# dueSkel.net
KiCad netlist of a schematic drawn in EAGLE
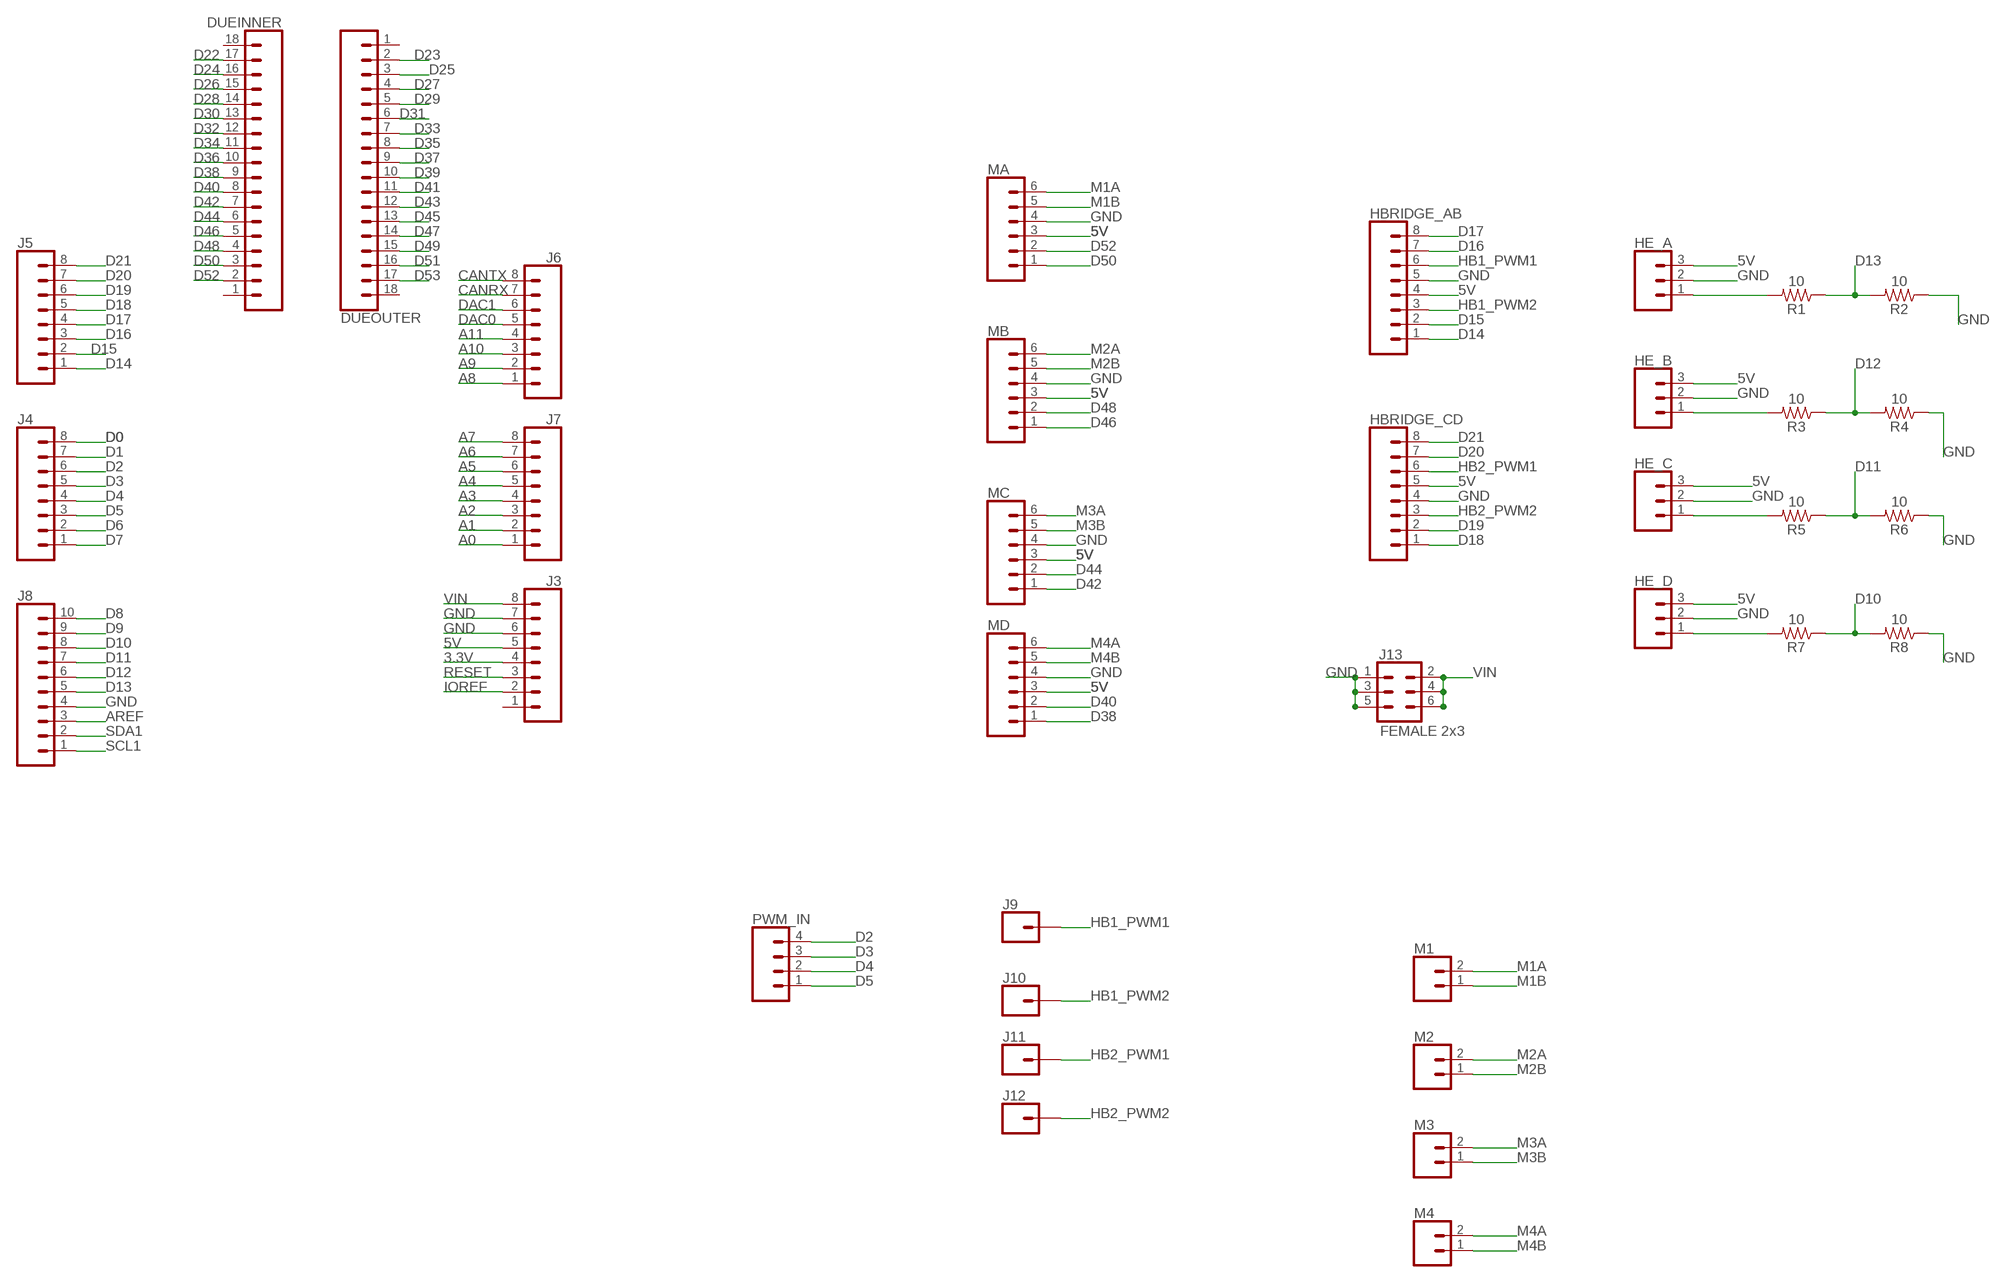
[diagram p0: schematic, sheet 1]

(export (version "E")
  (design (tool "Eeschema 10.0.6"))
  (components
    (comp (ref "DUEINNER")
      (value "CONN_18")
      (footprint "eagle-import:1X18")
      (libsource (lib "eagle-import") (part "CONN_18"))
    )
    (comp (ref "DUEOUTER")
      (value "CONN_18")
      (footprint "eagle-import:1X18")
      (libsource (lib "eagle-import") (part "CONN_18"))
    )
    (comp (ref "HBRIDGE_AB")
      (value "CONN_08\"")
      (footprint "eagle-import:1X08")
      (libsource (lib "eagle-import") (part "CONN_08{dblquote}"))
    )
    (comp (ref "HBRIDGE_CD")
      (value "CONN_08\"")
      (footprint "eagle-import:1X08")
      (libsource (lib "eagle-import") (part "CONN_08{dblquote}"))
    )
    (comp (ref "HE_A")
      (value "CONN_03")
      (footprint "eagle-import:1X03")
      (libsource (lib "eagle-import") (part "CONN_03"))
    )
    (comp (ref "HE_B")
      (value "CONN_03")
      (footprint "eagle-import:1X03")
      (libsource (lib "eagle-import") (part "CONN_03"))
    )
    (comp (ref "HE_C")
      (value "CONN_03")
      (footprint "eagle-import:1X03")
      (libsource (lib "eagle-import") (part "CONN_03"))
    )
    (comp (ref "HE_D")
      (value "CONN_03")
      (footprint "eagle-import:1X03")
      (libsource (lib "eagle-import") (part "CONN_03"))
    )
    (comp (ref "J3")
      (value "CONN_08\"")
      (footprint "eagle-import:1X08")
      (libsource (lib "eagle-import") (part "CONN_08{dblquote}"))
    )
    (comp (ref "J4")
      (value "CONN_08\"")
      (footprint "eagle-import:1X08")
      (libsource (lib "eagle-import") (part "CONN_08{dblquote}"))
    )
    (comp (ref "J5")
      (value "CONN_08\"")
      (footprint "eagle-import:1X08")
      (libsource (lib "eagle-import") (part "CONN_08{dblquote}"))
    )
    (comp (ref "J6")
      (value "CONN_08\"")
      (footprint "eagle-import:1X08")
      (libsource (lib "eagle-import") (part "CONN_08{dblquote}"))
    )
    (comp (ref "J7")
      (value "CONN_08\"")
      (footprint "eagle-import:1X08")
      (libsource (lib "eagle-import") (part "CONN_08{dblquote}"))
    )
    (comp (ref "J8")
      (value "CONN_10\"")
      (footprint "eagle-import:1X10")
      (libsource (lib "eagle-import") (part "CONN_10{dblquote}"))
    )
    (comp (ref "J9")
      (value "CONN_01")
      (footprint "eagle-import:1X01")
      (libsource (lib "eagle-import") (part "CONN_01"))
    )
    (comp (ref "J10")
      (value "CONN_01")
      (footprint "eagle-import:1X01")
      (libsource (lib "eagle-import") (part "CONN_01"))
    )
    (comp (ref "J11")
      (value "CONN_01")
      (footprint "eagle-import:1X01")
      (libsource (lib "eagle-import") (part "CONN_01"))
    )
    (comp (ref "J12")
      (value "CONN_01")
      (footprint "eagle-import:1X01")
      (libsource (lib "eagle-import") (part "CONN_01"))
    )
    (comp (ref "J13")
      (value "FEMALE 2x3")
      (footprint "eagle-import:2X3")
      (libsource (lib "eagle-import") (part "CONN_03X2FEMALE"))
    )
    (comp (ref "M1")
      (value "CONN_02")
      (footprint "eagle-import:1X02")
      (libsource (lib "eagle-import") (part "CONN_02"))
    )
    (comp (ref "M2")
      (value "CONN_02")
      (footprint "eagle-import:1X02")
      (libsource (lib "eagle-import") (part "CONN_02"))
    )
    (comp (ref "M3")
      (value "CONN_02")
      (footprint "eagle-import:1X02")
      (libsource (lib "eagle-import") (part "CONN_02"))
    )
    (comp (ref "M4")
      (value "CONN_02")
      (footprint "eagle-import:1X02")
      (libsource (lib "eagle-import") (part "CONN_02"))
    )
    (comp (ref "MA")
      (value "CONN_06SILK_FEMALE_PTH")
      (footprint "eagle-import:1X06")
      (libsource (lib "eagle-import") (part "CONN_06SILK_FEMALE_PTH"))
    )
    (comp (ref "MB")
      (value "CONN_06SILK_FEMALE_PTH")
      (footprint "eagle-import:1X06")
      (libsource (lib "eagle-import") (part "CONN_06SILK_FEMALE_PTH"))
    )
    (comp (ref "MC")
      (value "CONN_06SILK_FEMALE_PTH")
      (footprint "eagle-import:1X06")
      (libsource (lib "eagle-import") (part "CONN_06SILK_FEMALE_PTH"))
    )
    (comp (ref "MD")
      (value "CONN_06SILK_FEMALE_PTH")
      (footprint "eagle-import:1X06")
      (libsource (lib "eagle-import") (part "CONN_06SILK_FEMALE_PTH"))
    )
    (comp (ref "PWM_IN")
      (value "CONN_04")
      (footprint "eagle-import:1X04")
      (libsource (lib "eagle-import") (part "CONN_04"))
    )
    (comp (ref "R1")
      (value "10")
      (footprint "eagle-import:AXIAL-0.3")
      (libsource (lib "eagle-import") (part "10OHM-HORIZ-1/4W-1%"))
    )
    (comp (ref "R2")
      (value "10")
      (footprint "eagle-import:AXIAL-0.3")
      (libsource (lib "eagle-import") (part "10OHM-HORIZ-1/4W-1%"))
    )
    (comp (ref "R3")
      (value "10")
      (footprint "eagle-import:AXIAL-0.3")
      (libsource (lib "eagle-import") (part "10OHM-HORIZ-1/4W-1%"))
    )
    (comp (ref "R4")
      (value "10")
      (footprint "eagle-import:AXIAL-0.3")
      (libsource (lib "eagle-import") (part "10OHM-HORIZ-1/4W-1%"))
    )
    (comp (ref "R5")
      (value "10")
      (footprint "eagle-import:AXIAL-0.3")
      (libsource (lib "eagle-import") (part "10OHM-HORIZ-1/4W-1%"))
    )
    (comp (ref "R6")
      (value "10")
      (footprint "eagle-import:AXIAL-0.3")
      (libsource (lib "eagle-import") (part "10OHM-HORIZ-1/4W-1%"))
    )
    (comp (ref "R7")
      (value "10")
      (footprint "eagle-import:AXIAL-0.3")
      (libsource (lib "eagle-import") (part "10OHM-HORIZ-1/4W-1%"))
    )
    (comp (ref "R8")
      (value "10")
      (footprint "eagle-import:AXIAL-0.3")
      (libsource (lib "eagle-import") (part "10OHM-HORIZ-1/4W-1%"))
    )
  )
  (nets
    (net (code "1") (name "/3.3V") (class "Default")
      (node (ref "J3") (pin "4") (pinfunction "4_4") (pintype "passive"))
    )
    (net (code "2") (name "/5V") (class "Default")
      (node (ref "HBRIDGE_AB") (pin "4") (pinfunction "4_4") (pintype "passive"))
      (node (ref "HBRIDGE_CD") (pin "5") (pinfunction "5_5") (pintype "passive"))
      (node (ref "HE_A") (pin "3") (pinfunction "3_3") (pintype "passive"))
      (node (ref "HE_B") (pin "3") (pinfunction "3_3") (pintype "passive"))
      (node (ref "HE_C") (pin "3") (pinfunction "3_3") (pintype "passive"))
      (node (ref "HE_D") (pin "3") (pinfunction "3_3") (pintype "passive"))
      (node (ref "J3") (pin "5") (pinfunction "5_5") (pintype "passive"))
      (node (ref "MA") (pin "3") (pinfunction "3_3") (pintype "passive"))
      (node (ref "MB") (pin "3") (pinfunction "3_3") (pintype "passive"))
      (node (ref "MC") (pin "3") (pinfunction "3_3") (pintype "passive"))
      (node (ref "MD") (pin "3") (pinfunction "3_3") (pintype "passive"))
    )
    (net (code "3") (name "/A0") (class "Default")
      (node (ref "J7") (pin "1") (pinfunction "1_1") (pintype "passive"))
    )
    (net (code "4") (name "/A1") (class "Default")
      (node (ref "J7") (pin "2") (pinfunction "2_2") (pintype "passive"))
    )
    (net (code "5") (name "/A2") (class "Default")
      (node (ref "J7") (pin "3") (pinfunction "3_3") (pintype "passive"))
    )
    (net (code "6") (name "/A3") (class "Default")
      (node (ref "J7") (pin "4") (pinfunction "4_4") (pintype "passive"))
    )
    (net (code "7") (name "/A4") (class "Default")
      (node (ref "J7") (pin "5") (pinfunction "5_5") (pintype "passive"))
    )
    (net (code "8") (name "/A5") (class "Default")
      (node (ref "J7") (pin "6") (pinfunction "6_6") (pintype "passive"))
    )
    (net (code "9") (name "/A6") (class "Default")
      (node (ref "J7") (pin "7") (pinfunction "7_7") (pintype "passive"))
    )
    (net (code "10") (name "/A7") (class "Default")
      (node (ref "J7") (pin "8") (pinfunction "8_8") (pintype "passive"))
    )
    (net (code "11") (name "/A8") (class "Default")
      (node (ref "J6") (pin "1") (pinfunction "1_1") (pintype "passive"))
    )
    (net (code "12") (name "/A9") (class "Default")
      (node (ref "J6") (pin "2") (pinfunction "2_2") (pintype "passive"))
    )
    (net (code "13") (name "/A10") (class "Default")
      (node (ref "J6") (pin "3") (pinfunction "3_3") (pintype "passive"))
    )
    (net (code "14") (name "/A11") (class "Default")
      (node (ref "J6") (pin "4") (pinfunction "4_4") (pintype "passive"))
    )
    (net (code "15") (name "/AREF") (class "Default")
      (node (ref "J8") (pin "3") (pinfunction "3_3") (pintype "passive"))
    )
    (net (code "16") (name "/CANRX") (class "Default")
      (node (ref "J6") (pin "7") (pinfunction "7_7") (pintype "passive"))
    )
    (net (code "17") (name "/CANTX") (class "Default")
      (node (ref "J6") (pin "8") (pinfunction "8_8") (pintype "passive"))
    )
    (net (code "18") (name "/D0") (class "Default")
      (node (ref "J4") (pin "8") (pinfunction "8_8") (pintype "passive"))
    )
    (net (code "19") (name "/D1") (class "Default")
      (node (ref "J4") (pin "7") (pinfunction "7_7") (pintype "passive"))
    )
    (net (code "20") (name "/D2") (class "Default")
      (node (ref "J4") (pin "6") (pinfunction "6_6") (pintype "passive"))
      (node (ref "PWM_IN") (pin "4") (pinfunction "4_4") (pintype "passive"))
    )
    (net (code "21") (name "/D3") (class "Default")
      (node (ref "J4") (pin "5") (pinfunction "5_5") (pintype "passive"))
      (node (ref "PWM_IN") (pin "3") (pinfunction "3_3") (pintype "passive"))
    )
    (net (code "22") (name "/D4") (class "Default")
      (node (ref "J4") (pin "4") (pinfunction "4_4") (pintype "passive"))
      (node (ref "PWM_IN") (pin "2") (pinfunction "2_2") (pintype "passive"))
    )
    (net (code "23") (name "/D5") (class "Default")
      (node (ref "J4") (pin "3") (pinfunction "3_3") (pintype "passive"))
      (node (ref "PWM_IN") (pin "1") (pinfunction "1_1") (pintype "passive"))
    )
    (net (code "24") (name "/D6") (class "Default")
      (node (ref "J4") (pin "2") (pinfunction "2_2") (pintype "passive"))
    )
    (net (code "25") (name "/D7") (class "Default")
      (node (ref "J4") (pin "1") (pinfunction "1_1") (pintype "passive"))
    )
    (net (code "26") (name "/D8") (class "Default")
      (node (ref "J8") (pin "10") (pinfunction "10_10") (pintype "passive"))
    )
    (net (code "27") (name "/D9") (class "Default")
      (node (ref "J8") (pin "9") (pinfunction "9_9") (pintype "passive"))
    )
    (net (code "28") (name "/D10") (class "Default")
      (node (ref "J8") (pin "8") (pinfunction "8_8") (pintype "passive"))
      (node (ref "R7") (pin "P$1") (pinfunction "1_P$1") (pintype "passive"))
      (node (ref "R8") (pin "P$2") (pinfunction "2_P$2") (pintype "passive"))
    )
    (net (code "29") (name "/D11") (class "Default")
      (node (ref "J8") (pin "7") (pinfunction "7_7") (pintype "passive"))
      (node (ref "R5") (pin "P$1") (pinfunction "1_P$1") (pintype "passive"))
      (node (ref "R6") (pin "P$2") (pinfunction "2_P$2") (pintype "passive"))
    )
    (net (code "30") (name "/D12") (class "Default")
      (node (ref "J8") (pin "6") (pinfunction "6_6") (pintype "passive"))
      (node (ref "R3") (pin "P$1") (pinfunction "1_P$1") (pintype "passive"))
      (node (ref "R4") (pin "P$2") (pinfunction "2_P$2") (pintype "passive"))
    )
    (net (code "31") (name "/D13") (class "Default")
      (node (ref "J8") (pin "5") (pinfunction "5_5") (pintype "passive"))
      (node (ref "R1") (pin "P$1") (pinfunction "1_P$1") (pintype "passive"))
      (node (ref "R2") (pin "P$2") (pinfunction "2_P$2") (pintype "passive"))
    )
    (net (code "32") (name "/D14") (class "Default")
      (node (ref "HBRIDGE_AB") (pin "1") (pinfunction "1_1") (pintype "passive"))
      (node (ref "J5") (pin "1") (pinfunction "1_1") (pintype "passive"))
    )
    (net (code "33") (name "/D15") (class "Default")
      (node (ref "HBRIDGE_AB") (pin "2") (pinfunction "2_2") (pintype "passive"))
      (node (ref "J5") (pin "2") (pinfunction "2_2") (pintype "passive"))
    )
    (net (code "34") (name "/D16") (class "Default")
      (node (ref "HBRIDGE_AB") (pin "7") (pinfunction "7_7") (pintype "passive"))
      (node (ref "J5") (pin "3") (pinfunction "3_3") (pintype "passive"))
    )
    (net (code "35") (name "/D17") (class "Default")
      (node (ref "HBRIDGE_AB") (pin "8") (pinfunction "8_8") (pintype "passive"))
      (node (ref "J5") (pin "4") (pinfunction "4_4") (pintype "passive"))
    )
    (net (code "36") (name "/D18") (class "Default")
      (node (ref "HBRIDGE_CD") (pin "1") (pinfunction "1_1") (pintype "passive"))
      (node (ref "J5") (pin "5") (pinfunction "5_5") (pintype "passive"))
    )
    (net (code "37") (name "/D19") (class "Default")
      (node (ref "HBRIDGE_CD") (pin "2") (pinfunction "2_2") (pintype "passive"))
      (node (ref "J5") (pin "6") (pinfunction "6_6") (pintype "passive"))
    )
    (net (code "38") (name "/D20") (class "Default")
      (node (ref "HBRIDGE_CD") (pin "7") (pinfunction "7_7") (pintype "passive"))
      (node (ref "J5") (pin "7") (pinfunction "7_7") (pintype "passive"))
    )
    (net (code "39") (name "/D21") (class "Default")
      (node (ref "HBRIDGE_CD") (pin "8") (pinfunction "8_8") (pintype "passive"))
      (node (ref "J5") (pin "8") (pinfunction "8_8") (pintype "passive"))
    )
    (net (code "40") (name "/D22") (class "Default")
      (node (ref "DUEINNER") (pin "17") (pinfunction "17_17") (pintype "passive"))
    )
    (net (code "41") (name "/D23") (class "Default")
      (node (ref "DUEOUTER") (pin "2") (pinfunction "2_2") (pintype "passive"))
    )
    (net (code "42") (name "/D24") (class "Default")
      (node (ref "DUEINNER") (pin "16") (pinfunction "16_16") (pintype "passive"))
    )
    (net (code "43") (name "/D25") (class "Default")
      (node (ref "DUEOUTER") (pin "3") (pinfunction "3_3") (pintype "passive"))
    )
    (net (code "44") (name "/D26") (class "Default")
      (node (ref "DUEINNER") (pin "15") (pinfunction "15_15") (pintype "passive"))
    )
    (net (code "45") (name "/D27") (class "Default")
      (node (ref "DUEOUTER") (pin "4") (pinfunction "4_4") (pintype "passive"))
    )
    (net (code "46") (name "/D28") (class "Default")
      (node (ref "DUEINNER") (pin "14") (pinfunction "14_14") (pintype "passive"))
    )
    (net (code "47") (name "/D29") (class "Default")
      (node (ref "DUEOUTER") (pin "5") (pinfunction "5_5") (pintype "passive"))
    )
    (net (code "48") (name "/D30") (class "Default")
      (node (ref "DUEINNER") (pin "13") (pinfunction "13_13") (pintype "passive"))
    )
    (net (code "49") (name "/D31") (class "Default")
      (node (ref "DUEOUTER") (pin "6") (pinfunction "6_6") (pintype "passive"))
    )
    (net (code "50") (name "/D32") (class "Default")
      (node (ref "DUEINNER") (pin "12") (pinfunction "12_12") (pintype "passive"))
    )
    (net (code "51") (name "/D33") (class "Default")
      (node (ref "DUEOUTER") (pin "7") (pinfunction "7_7") (pintype "passive"))
    )
    (net (code "52") (name "/D34") (class "Default")
      (node (ref "DUEINNER") (pin "11") (pinfunction "11_11") (pintype "passive"))
    )
    (net (code "53") (name "/D35") (class "Default")
      (node (ref "DUEOUTER") (pin "8") (pinfunction "8_8") (pintype "passive"))
    )
    (net (code "54") (name "/D36") (class "Default")
      (node (ref "DUEINNER") (pin "10") (pinfunction "10_10") (pintype "passive"))
    )
    (net (code "55") (name "/D37") (class "Default")
      (node (ref "DUEOUTER") (pin "9") (pinfunction "9_9") (pintype "passive"))
    )
    (net (code "56") (name "/D38") (class "Default")
      (node (ref "DUEINNER") (pin "9") (pinfunction "9_9") (pintype "passive"))
      (node (ref "MD") (pin "1") (pinfunction "1_1") (pintype "passive"))
    )
    (net (code "57") (name "/D39") (class "Default")
      (node (ref "DUEOUTER") (pin "10") (pinfunction "10_10") (pintype "passive"))
    )
    (net (code "58") (name "/D40") (class "Default")
      (node (ref "DUEINNER") (pin "8") (pinfunction "8_8") (pintype "passive"))
      (node (ref "MD") (pin "2") (pinfunction "2_2") (pintype "passive"))
    )
    (net (code "59") (name "/D41") (class "Default")
      (node (ref "DUEOUTER") (pin "11") (pinfunction "11_11") (pintype "passive"))
    )
    (net (code "60") (name "/D42") (class "Default")
      (node (ref "DUEINNER") (pin "7") (pinfunction "7_7") (pintype "passive"))
      (node (ref "MC") (pin "1") (pinfunction "1_1") (pintype "passive"))
    )
    (net (code "61") (name "/D43") (class "Default")
      (node (ref "DUEOUTER") (pin "12") (pinfunction "12_12") (pintype "passive"))
    )
    (net (code "62") (name "/D44") (class "Default")
      (node (ref "DUEINNER") (pin "6") (pinfunction "6_6") (pintype "passive"))
      (node (ref "MC") (pin "2") (pinfunction "2_2") (pintype "passive"))
    )
    (net (code "63") (name "/D45") (class "Default")
      (node (ref "DUEOUTER") (pin "13") (pinfunction "13_13") (pintype "passive"))
    )
    (net (code "64") (name "/D46") (class "Default")
      (node (ref "DUEINNER") (pin "5") (pinfunction "5_5") (pintype "passive"))
      (node (ref "MB") (pin "1") (pinfunction "1_1") (pintype "passive"))
    )
    (net (code "65") (name "/D47") (class "Default")
      (node (ref "DUEOUTER") (pin "14") (pinfunction "14_14") (pintype "passive"))
    )
    (net (code "66") (name "/D48") (class "Default")
      (node (ref "DUEINNER") (pin "4") (pinfunction "4_4") (pintype "passive"))
      (node (ref "MB") (pin "2") (pinfunction "2_2") (pintype "passive"))
    )
    (net (code "67") (name "/D49") (class "Default")
      (node (ref "DUEOUTER") (pin "15") (pinfunction "15_15") (pintype "passive"))
    )
    (net (code "68") (name "/D50") (class "Default")
      (node (ref "DUEINNER") (pin "3") (pinfunction "3_3") (pintype "passive"))
      (node (ref "MA") (pin "1") (pinfunction "1_1") (pintype "passive"))
    )
    (net (code "69") (name "/D51") (class "Default")
      (node (ref "DUEOUTER") (pin "16") (pinfunction "16_16") (pintype "passive"))
    )
    (net (code "70") (name "/D52") (class "Default")
      (node (ref "DUEINNER") (pin "2") (pinfunction "2_2") (pintype "passive"))
      (node (ref "MA") (pin "2") (pinfunction "2_2") (pintype "passive"))
    )
    (net (code "71") (name "/D53") (class "Default")
      (node (ref "DUEOUTER") (pin "17") (pinfunction "17_17") (pintype "passive"))
    )
    (net (code "72") (name "/DAC0") (class "Default")
      (node (ref "J6") (pin "5") (pinfunction "5_5") (pintype "passive"))
    )
    (net (code "73") (name "/DAC1") (class "Default")
      (node (ref "J6") (pin "6") (pinfunction "6_6") (pintype "passive"))
    )
    (net (code "74") (name "/GND") (class "Default")
      (node (ref "HBRIDGE_AB") (pin "5") (pinfunction "5_5") (pintype "passive"))
      (node (ref "HBRIDGE_CD") (pin "4") (pinfunction "4_4") (pintype "passive"))
      (node (ref "HE_A") (pin "2") (pinfunction "2_2") (pintype "passive"))
      (node (ref "HE_B") (pin "2") (pinfunction "2_2") (pintype "passive"))
      (node (ref "HE_C") (pin "2") (pinfunction "2_2") (pintype "passive"))
      (node (ref "HE_D") (pin "2") (pinfunction "2_2") (pintype "passive"))
      (node (ref "J13") (pin "1") (pinfunction "1_1") (pintype "bidirectional"))
      (node (ref "J13") (pin "3") (pinfunction "3_3") (pintype "bidirectional"))
      (node (ref "J13") (pin "5") (pinfunction "5_5") (pintype "bidirectional"))
      (node (ref "J3") (pin "6") (pinfunction "6_6") (pintype "passive"))
      (node (ref "J3") (pin "7") (pinfunction "7_7") (pintype "passive"))
      (node (ref "J8") (pin "4") (pinfunction "4_4") (pintype "passive"))
      (node (ref "MA") (pin "4") (pinfunction "4_4") (pintype "passive"))
      (node (ref "MB") (pin "4") (pinfunction "4_4") (pintype "passive"))
      (node (ref "MC") (pin "4") (pinfunction "4_4") (pintype "passive"))
      (node (ref "MD") (pin "4") (pinfunction "4_4") (pintype "passive"))
      (node (ref "R2") (pin "P$1") (pinfunction "1_P$1") (pintype "passive"))
      (node (ref "R4") (pin "P$1") (pinfunction "1_P$1") (pintype "passive"))
      (node (ref "R6") (pin "P$1") (pinfunction "1_P$1") (pintype "passive"))
      (node (ref "R8") (pin "P$1") (pinfunction "1_P$1") (pintype "passive"))
    )
    (net (code "75") (name "/HB1_PWM1") (class "Default")
      (node (ref "HBRIDGE_AB") (pin "6") (pinfunction "6_6") (pintype "passive"))
      (node (ref "J9") (pin "1") (pinfunction "1_1") (pintype "passive"))
    )
    (net (code "76") (name "/HB1_PWM2") (class "Default")
      (node (ref "HBRIDGE_AB") (pin "3") (pinfunction "3_3") (pintype "passive"))
      (node (ref "J10") (pin "1") (pinfunction "1_1") (pintype "passive"))
    )
    (net (code "77") (name "/HB2_PWM1") (class "Default")
      (node (ref "HBRIDGE_CD") (pin "6") (pinfunction "6_6") (pintype "passive"))
      (node (ref "J11") (pin "1") (pinfunction "1_1") (pintype "passive"))
    )
    (net (code "78") (name "/HB2_PWM2") (class "Default")
      (node (ref "HBRIDGE_CD") (pin "3") (pinfunction "3_3") (pintype "passive"))
      (node (ref "J12") (pin "1") (pinfunction "1_1") (pintype "passive"))
    )
    (net (code "79") (name "/IOREF") (class "Default")
      (node (ref "J3") (pin "2") (pinfunction "2_2") (pintype "passive"))
    )
    (net (code "80") (name "/M1A") (class "Default")
      (node (ref "M1") (pin "2") (pinfunction "2_2") (pintype "passive"))
      (node (ref "MA") (pin "6") (pinfunction "6_6") (pintype "passive"))
    )
    (net (code "81") (name "/M1B") (class "Default")
      (node (ref "M1") (pin "1") (pinfunction "1_1") (pintype "passive"))
      (node (ref "MA") (pin "5") (pinfunction "5_5") (pintype "passive"))
    )
    (net (code "82") (name "/M2A") (class "Default")
      (node (ref "M2") (pin "2") (pinfunction "2_2") (pintype "passive"))
      (node (ref "MB") (pin "6") (pinfunction "6_6") (pintype "passive"))
    )
    (net (code "83") (name "/M2B") (class "Default")
      (node (ref "M2") (pin "1") (pinfunction "1_1") (pintype "passive"))
      (node (ref "MB") (pin "5") (pinfunction "5_5") (pintype "passive"))
    )
    (net (code "84") (name "/M3A") (class "Default")
      (node (ref "M3") (pin "2") (pinfunction "2_2") (pintype "passive"))
      (node (ref "MC") (pin "6") (pinfunction "6_6") (pintype "passive"))
    )
    (net (code "85") (name "/M3B") (class "Default")
      (node (ref "M3") (pin "1") (pinfunction "1_1") (pintype "passive"))
      (node (ref "MC") (pin "5") (pinfunction "5_5") (pintype "passive"))
    )
    (net (code "86") (name "/M4A") (class "Default")
      (node (ref "M4") (pin "2") (pinfunction "2_2") (pintype "passive"))
      (node (ref "MD") (pin "6") (pinfunction "6_6") (pintype "passive"))
    )
    (net (code "87") (name "/M4B") (class "Default")
      (node (ref "M4") (pin "1") (pinfunction "1_1") (pintype "passive"))
      (node (ref "MD") (pin "5") (pinfunction "5_5") (pintype "passive"))
    )
    (net (code "88") (name "/RESET") (class "Default")
      (node (ref "J3") (pin "3") (pinfunction "3_3") (pintype "passive"))
    )
    (net (code "89") (name "/SCL1") (class "Default")
      (node (ref "J8") (pin "1") (pinfunction "1_1") (pintype "passive"))
    )
    (net (code "90") (name "/SDA1") (class "Default")
      (node (ref "J8") (pin "2") (pinfunction "2_2") (pintype "passive"))
    )
    (net (code "91") (name "/VIN") (class "Default")
      (node (ref "J13") (pin "2") (pinfunction "2_2") (pintype "bidirectional"))
      (node (ref "J13") (pin "4") (pinfunction "4_4") (pintype "bidirectional"))
      (node (ref "J13") (pin "6") (pinfunction "6_6") (pintype "bidirectional"))
      (node (ref "J3") (pin "8") (pinfunction "8_8") (pintype "passive"))
    )
    (net (code "92") (name "Net-(R1-2)") (class "Default")
      (node (ref "HE_A") (pin "1") (pinfunction "1_1") (pintype "passive"))
      (node (ref "R1") (pin "P$2") (pinfunction "2_P$2") (pintype "passive"))
    )
    (net (code "93") (name "Net-(R3-2)") (class "Default")
      (node (ref "HE_B") (pin "1") (pinfunction "1_1") (pintype "passive"))
      (node (ref "R3") (pin "P$2") (pinfunction "2_P$2") (pintype "passive"))
    )
    (net (code "94") (name "Net-(R5-2)") (class "Default")
      (node (ref "HE_C") (pin "1") (pinfunction "1_1") (pintype "passive"))
      (node (ref "R5") (pin "P$2") (pinfunction "2_P$2") (pintype "passive"))
    )
    (net (code "95") (name "Net-(R7-2)") (class "Default")
      (node (ref "HE_D") (pin "1") (pinfunction "1_1") (pintype "passive"))
      (node (ref "R7") (pin "P$2") (pinfunction "2_P$2") (pintype "passive"))
    )
    (net (code "96") (name "unconnected-(DUEINNER-Pad1)") (class "Default")
      (node (ref "DUEINNER") (pin "1") (pinfunction "1_1") (pintype "passive"))
    )
    (net (code "97") (name "unconnected-(DUEINNER-Pad18)") (class "Default")
      (node (ref "DUEINNER") (pin "18") (pinfunction "18_18") (pintype "passive"))
    )
    (net (code "98") (name "unconnected-(DUEOUTER-Pad1)") (class "Default")
      (node (ref "DUEOUTER") (pin "1") (pinfunction "1_1") (pintype "passive"))
    )
    (net (code "99") (name "unconnected-(DUEOUTER-Pad18)") (class "Default")
      (node (ref "DUEOUTER") (pin "18") (pinfunction "18_18") (pintype "passive"))
    )
    (net (code "100") (name "unconnected-(J3-Pad1)") (class "Default")
      (node (ref "J3") (pin "1") (pinfunction "1_1") (pintype "passive"))
    )
  )
)
